# Day0_Aditya_Rizky_Maulana_13215007.net
KiCad netlist of a schematic drawn in EAGLE
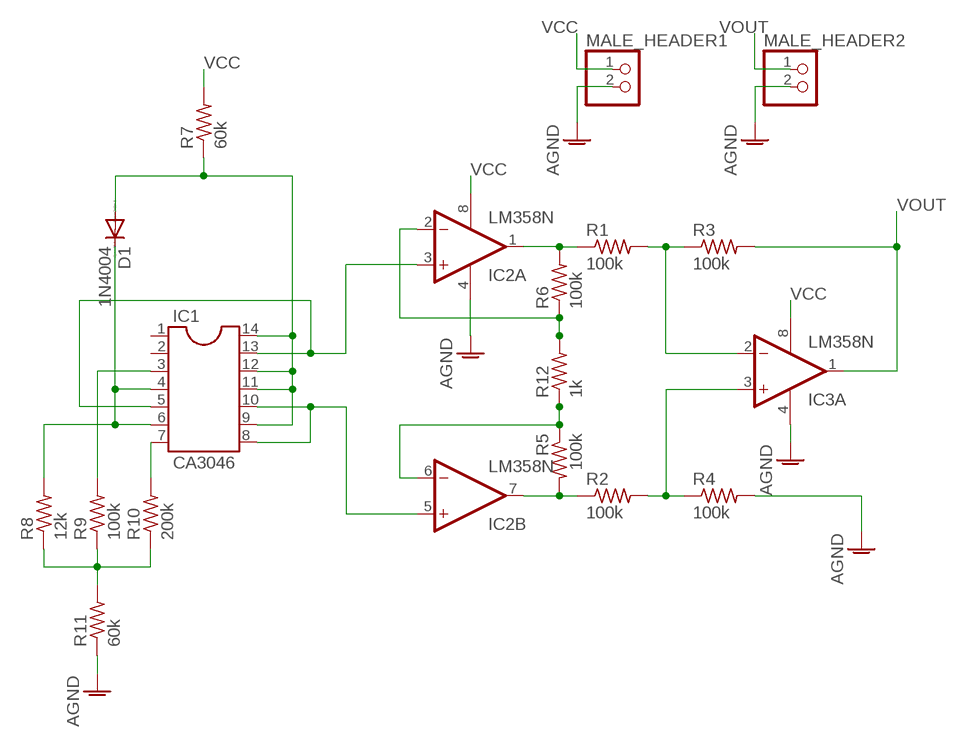
[diagram p0: schematic, sheet 1]

(export (version "E")
  (design (tool "Eeschema 10.0.6"))
  (components
    (comp (ref "D1")
      (value "1N4004")
      (footprint "eagle-import:DO41-10")
      (libsource (lib "eagle-import") (part "1N4004"))
    )
    (comp (ref "IC1")
      (value "CA3046")
      (footprint "eagle-import:DIL14")
      (libsource (lib "eagle-import") (part "DIL14"))
    )
    (comp (ref "IC2")
      (value "LM358N")
      (footprint "eagle-import:DIL08")
      (libsource (lib "eagle-import") (part "LM358N"))
    )
    (comp (ref "IC3")
      (value "LM358N")
      (footprint "eagle-import:DIL08")
      (libsource (lib "eagle-import") (part "LM358N"))
    )
    (comp (ref "MALE_HEADER1")
      (value "PINHD-1X2")
      (footprint "eagle-import:1X02")
      (libsource (lib "eagle-import") (part "PINHD-1X2"))
    )
    (comp (ref "MALE_HEADER2")
      (value "PINHD-1X2")
      (footprint "eagle-import:1X02")
      (libsource (lib "eagle-import") (part "PINHD-1X2"))
    )
    (comp (ref "R1")
      (value "100k")
      (footprint "eagle-import:0207_7")
      (libsource (lib "eagle-import") (part "R-US_0207/7"))
    )
    (comp (ref "R2")
      (value "100k")
      (footprint "eagle-import:0207_7")
      (libsource (lib "eagle-import") (part "R-US_0207/7"))
    )
    (comp (ref "R3")
      (value "100k")
      (footprint "eagle-import:0207_7")
      (libsource (lib "eagle-import") (part "R-US_0207/7"))
    )
    (comp (ref "R4")
      (value "100k")
      (footprint "eagle-import:0207_7")
      (libsource (lib "eagle-import") (part "R-US_0207/7"))
    )
    (comp (ref "R5")
      (value "100k")
      (footprint "eagle-import:0207_7")
      (libsource (lib "eagle-import") (part "R-US_0207/7"))
    )
    (comp (ref "R6")
      (value "100k")
      (footprint "eagle-import:0207_7")
      (libsource (lib "eagle-import") (part "R-US_0207/7"))
    )
    (comp (ref "R7")
      (value "60k")
      (footprint "eagle-import:0207_7")
      (libsource (lib "eagle-import") (part "R-US_0207/7"))
    )
    (comp (ref "R8")
      (value "12k")
      (footprint "eagle-import:0207_7")
      (libsource (lib "eagle-import") (part "R-US_0207/7"))
    )
    (comp (ref "R9")
      (value "100k")
      (footprint "eagle-import:0207_7")
      (libsource (lib "eagle-import") (part "R-US_0207/7"))
    )
    (comp (ref "R10")
      (value "200k")
      (footprint "eagle-import:0207_7")
      (libsource (lib "eagle-import") (part "R-US_0207/7"))
    )
    (comp (ref "R11")
      (value "60k")
      (footprint "eagle-import:0207_7")
      (libsource (lib "eagle-import") (part "R-US_0207/7"))
    )
    (comp (ref "R12")
      (value "1k")
      (footprint "eagle-import:0207_7")
      (libsource (lib "eagle-import") (part "R-US_0207/7"))
    )
  )
  (nets
    (net (code "1") (name "/VCC") (class "Default")
      (node (ref "IC2") (pin "8") (pinfunction "V+_8") (pintype "power_in"))
      (node (ref "IC3") (pin "8") (pinfunction "V+_8") (pintype "power_in"))
      (node (ref "MALE_HEADER1") (pin "1") (pinfunction "1_1") (pintype "passive"))
      (node (ref "R7") (pin "2") (pinfunction "2_2") (pintype "passive"))
    )
    (net (code "2") (name "/VOUT") (class "Default")
      (node (ref "IC3") (pin "1") (pinfunction "OUT_1") (pintype "output"))
      (node (ref "MALE_HEADER2") (pin "1") (pinfunction "1_1") (pintype "passive"))
      (node (ref "R3") (pin "2") (pinfunction "2_2") (pintype "passive"))
    )
    (net (code "3") (name "AGND") (class "Default")
      (node (ref "IC2") (pin "4") (pinfunction "V-_4") (pintype "power_in"))
      (node (ref "IC3") (pin "4") (pinfunction "V-_4") (pintype "power_in"))
      (node (ref "MALE_HEADER1") (pin "2") (pinfunction "2_2") (pintype "passive"))
      (node (ref "MALE_HEADER2") (pin "2") (pinfunction "2_2") (pintype "passive"))
      (node (ref "R11") (pin "1") (pinfunction "1_1") (pintype "passive"))
      (node (ref "R4") (pin "2") (pinfunction "2_2") (pintype "passive"))
    )
    (net (code "4") (name "Net-(D1-PadA)") (class "Default")
      (node (ref "D1") (pin "A") (pinfunction "A_A") (pintype "passive"))
      (node (ref "IC1") (pin "11") (pinfunction "11_11") (pintype "passive"))
      (node (ref "IC1") (pin "12") (pinfunction "12_12") (pintype "passive"))
      (node (ref "IC1") (pin "14") (pinfunction "14_14") (pintype "passive"))
      (node (ref "IC1") (pin "9") (pinfunction "9_9") (pintype "passive"))
      (node (ref "R7") (pin "1") (pinfunction "1_1") (pintype "passive"))
    )
    (net (code "5") (name "Net-(D1-PadC)") (class "Default")
      (node (ref "D1") (pin "C") (pinfunction "C_C") (pintype "passive"))
      (node (ref "IC1") (pin "4") (pinfunction "4_4") (pintype "passive"))
      (node (ref "IC1") (pin "6") (pinfunction "6_6") (pintype "passive"))
      (node (ref "R8") (pin "2") (pinfunction "2_2") (pintype "passive"))
    )
    (net (code "6") (name "Net-(IC1-Pad3)") (class "Default")
      (node (ref "IC1") (pin "3") (pinfunction "3_3") (pintype "passive"))
      (node (ref "R9") (pin "2") (pinfunction "2_2") (pintype "passive"))
    )
    (net (code "7") (name "Net-(IC1-Pad7)") (class "Default")
      (node (ref "IC1") (pin "7") (pinfunction "7_7") (pintype "passive"))
      (node (ref "R10") (pin "2") (pinfunction "2_2") (pintype "passive"))
    )
    (net (code "8") (name "Net-(IC2A-+IN)") (class "Default")
      (node (ref "IC1") (pin "13") (pinfunction "13_13") (pintype "passive"))
      (node (ref "IC1") (pin "5") (pinfunction "5_5") (pintype "passive"))
      (node (ref "IC2") (pin "3") (pinfunction "+IN_3") (pintype "input"))
    )
    (net (code "9") (name "Net-(IC2A--IN)") (class "Default")
      (node (ref "IC2") (pin "2") (pinfunction "-IN_2") (pintype "input"))
      (node (ref "R12") (pin "2") (pinfunction "2_2") (pintype "passive"))
      (node (ref "R6") (pin "1") (pinfunction "1_1") (pintype "passive"))
    )
    (net (code "10") (name "Net-(IC2A-OUT)") (class "Default")
      (node (ref "IC2") (pin "1") (pinfunction "OUT_1") (pintype "output"))
      (node (ref "R1") (pin "1") (pinfunction "1_1") (pintype "passive"))
      (node (ref "R6") (pin "2") (pinfunction "2_2") (pintype "passive"))
    )
    (net (code "11") (name "Net-(IC2B-+IN)") (class "Default")
      (node (ref "IC1") (pin "10") (pinfunction "10_10") (pintype "passive"))
      (node (ref "IC1") (pin "8") (pinfunction "8_8") (pintype "passive"))
      (node (ref "IC2") (pin "5") (pinfunction "+IN_5") (pintype "input"))
    )
    (net (code "12") (name "Net-(IC2B--IN)") (class "Default")
      (node (ref "IC2") (pin "6") (pinfunction "-IN_6") (pintype "input"))
      (node (ref "R12") (pin "1") (pinfunction "1_1") (pintype "passive"))
      (node (ref "R5") (pin "1") (pinfunction "1_1") (pintype "passive"))
    )
    (net (code "13") (name "Net-(IC2B-OUT)") (class "Default")
      (node (ref "IC2") (pin "7") (pinfunction "OUT_7") (pintype "output"))
      (node (ref "R2") (pin "1") (pinfunction "1_1") (pintype "passive"))
      (node (ref "R5") (pin "2") (pinfunction "2_2") (pintype "passive"))
    )
    (net (code "14") (name "Net-(IC3A-+IN)") (class "Default")
      (node (ref "IC3") (pin "3") (pinfunction "+IN_3") (pintype "input"))
      (node (ref "R2") (pin "2") (pinfunction "2_2") (pintype "passive"))
      (node (ref "R4") (pin "1") (pinfunction "1_1") (pintype "passive"))
    )
    (net (code "15") (name "Net-(IC3A--IN)") (class "Default")
      (node (ref "IC3") (pin "2") (pinfunction "-IN_2") (pintype "input"))
      (node (ref "R1") (pin "2") (pinfunction "2_2") (pintype "passive"))
      (node (ref "R3") (pin "1") (pinfunction "1_1") (pintype "passive"))
    )
    (net (code "16") (name "Net-(R10-Pad1)") (class "Default")
      (node (ref "R10") (pin "1") (pinfunction "1_1") (pintype "passive"))
      (node (ref "R11") (pin "2") (pinfunction "2_2") (pintype "passive"))
      (node (ref "R8") (pin "1") (pinfunction "1_1") (pintype "passive"))
      (node (ref "R9") (pin "1") (pinfunction "1_1") (pintype "passive"))
    )
    (net (code "17") (name "unconnected-(IC1-Pad1)") (class "Default")
      (node (ref "IC1") (pin "1") (pinfunction "1_1") (pintype "passive"))
    )
    (net (code "18") (name "unconnected-(IC1-Pad2)") (class "Default")
      (node (ref "IC1") (pin "2") (pinfunction "2_2") (pintype "passive"))
    )
  )
)
